# MOUTING.net
KiCad netlist of a schematic drawn in Altium Designer
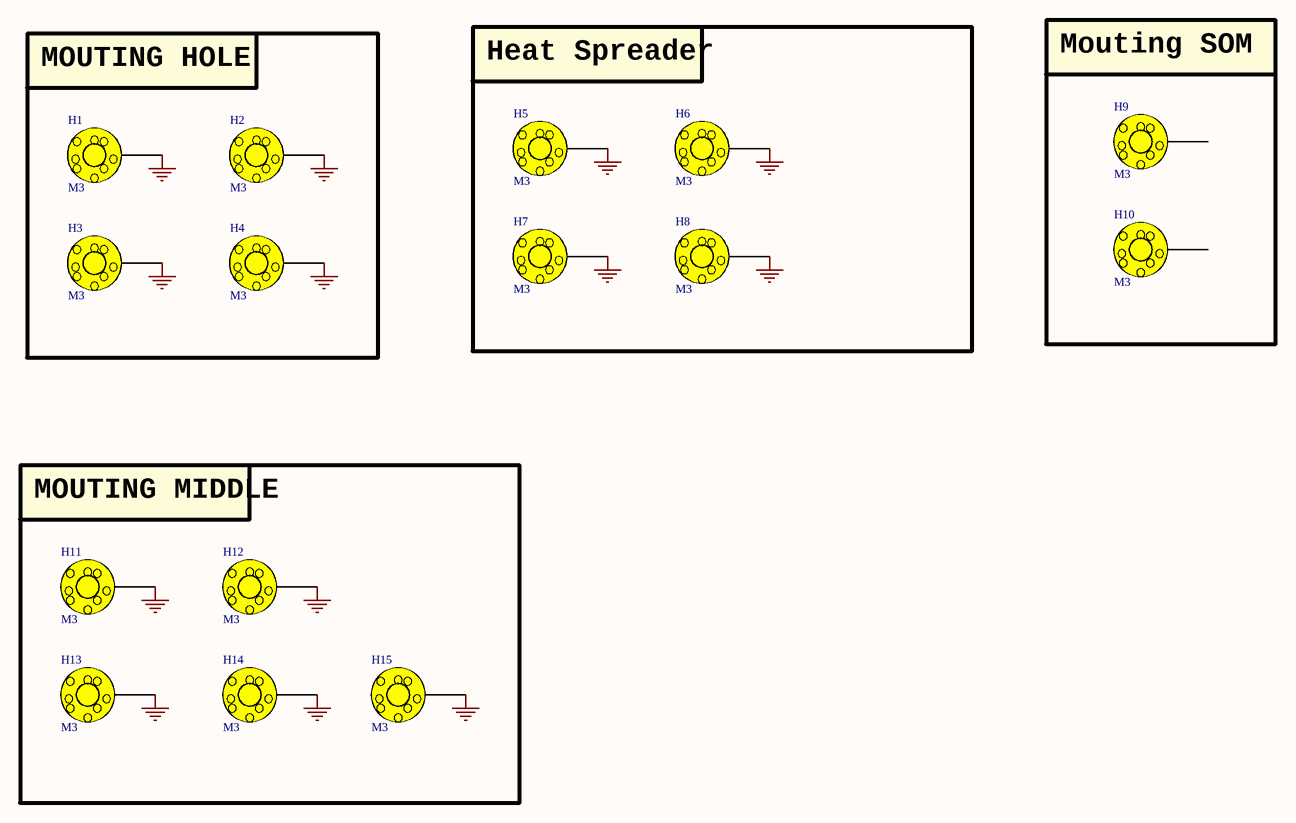
[diagram p0: MOUTING.SchDoc]

(export (version "E")
  (design (tool "Eeschema 10.0.6"))
  (components
    (comp (ref "H1") (value "M3") (footprint "HEX-M3_NoVia") (libsource (lib "hex_M3") (part "HEX-M3")))
    (comp (ref "H2") (value "M3") (footprint "HEX-M3_NoVia") (libsource (lib "hex_M3") (part "HEX-M3")))
    (comp (ref "H3") (value "M3") (footprint "HEX-M3_NoVia") (libsource (lib "hex_M3") (part "HEX-M3")))
    (comp (ref "H4") (value "M3") (footprint "HEX-M3_NoVia") (libsource (lib "hex_M3") (part "HEX-M3")))
    (comp (ref "H5") (value "M3") (footprint "HEX-M3_NoVia") (libsource (lib "hex_M3") (part "HEX-M3")))
    (comp (ref "H6") (value "M3") (footprint "HEX-M3_NoVia") (libsource (lib "hex_M3") (part "HEX-M3")))
    (comp (ref "H7") (value "M3") (footprint "HEX-M3_NoVia") (libsource (lib "hex_M3") (part "HEX-M3")))
    (comp (ref "H8") (value "M3") (footprint "HEX-M3_NoVia") (libsource (lib "hex_M3") (part "HEX-M3")))
    (comp (ref "H9")
      (value "M3")
      (footprint "Testpoint_TH_D450H250")
      (libsource (lib "hex_M3") (part "HEX-M3"))
    )
    (comp (ref "H10")
      (value "M3")
      (footprint "Testpoint_TH_D450H250")
      (libsource (lib "hex_M3") (part "HEX-M3"))
    )
    (comp (ref "H11") (value "M3") (footprint "HEX-M3_NoVia") (libsource (lib "hex_M3") (part "HEX-M3")))
    (comp (ref "H12") (value "M3") (footprint "HEX-M3_NoVia") (libsource (lib "hex_M3") (part "HEX-M3")))
    (comp (ref "H13") (value "M3") (footprint "HEX-M3_NoVia") (libsource (lib "hex_M3") (part "HEX-M3")))
    (comp (ref "H14") (value "M3") (footprint "HEX-M3_NoVia") (libsource (lib "hex_M3") (part "HEX-M3")))
    (comp (ref "H15") (value "M3") (footprint "HEX-M3_NoVia") (libsource (lib "hex_M3") (part "HEX-M3")))
  )
  (nets
    (net (code "1") (name "GND") (class "Default")
      (node (ref "H1") (pin "1") (pinfunction "1_1") (pintype "power_in"))
      (node (ref "H11") (pin "1") (pinfunction "1_1") (pintype "power_in"))
      (node (ref "H12") (pin "1") (pinfunction "1_1") (pintype "power_in"))
      (node (ref "H13") (pin "1") (pinfunction "1_1") (pintype "power_in"))
      (node (ref "H14") (pin "1") (pinfunction "1_1") (pintype "power_in"))
      (node (ref "H15") (pin "1") (pinfunction "1_1") (pintype "power_in"))
      (node (ref "H2") (pin "1") (pinfunction "1_1") (pintype "power_in"))
      (node (ref "H3") (pin "1") (pinfunction "1_1") (pintype "power_in"))
      (node (ref "H4") (pin "1") (pinfunction "1_1") (pintype "power_in"))
      (node (ref "H5") (pin "1") (pinfunction "1_1") (pintype "power_in"))
      (node (ref "H6") (pin "1") (pinfunction "1_1") (pintype "power_in"))
      (node (ref "H7") (pin "1") (pinfunction "1_1") (pintype "power_in"))
      (node (ref "H8") (pin "1") (pinfunction "1_1") (pintype "power_in"))
    )
    (net (code "2") (name "unconnected-(H9-Pad1)") (class "Default")
      (node (ref "H9") (pin "1") (pinfunction "1_1") (pintype "power_in"))
    )
    (net (code "3") (name "unconnected-(H10-Pad1)") (class "Default")
      (node (ref "H10") (pin "1") (pinfunction "1_1") (pintype "power_in"))
    )
  )
)
